# MC.net
KiCad netlist of a schematic drawn in EAGLE
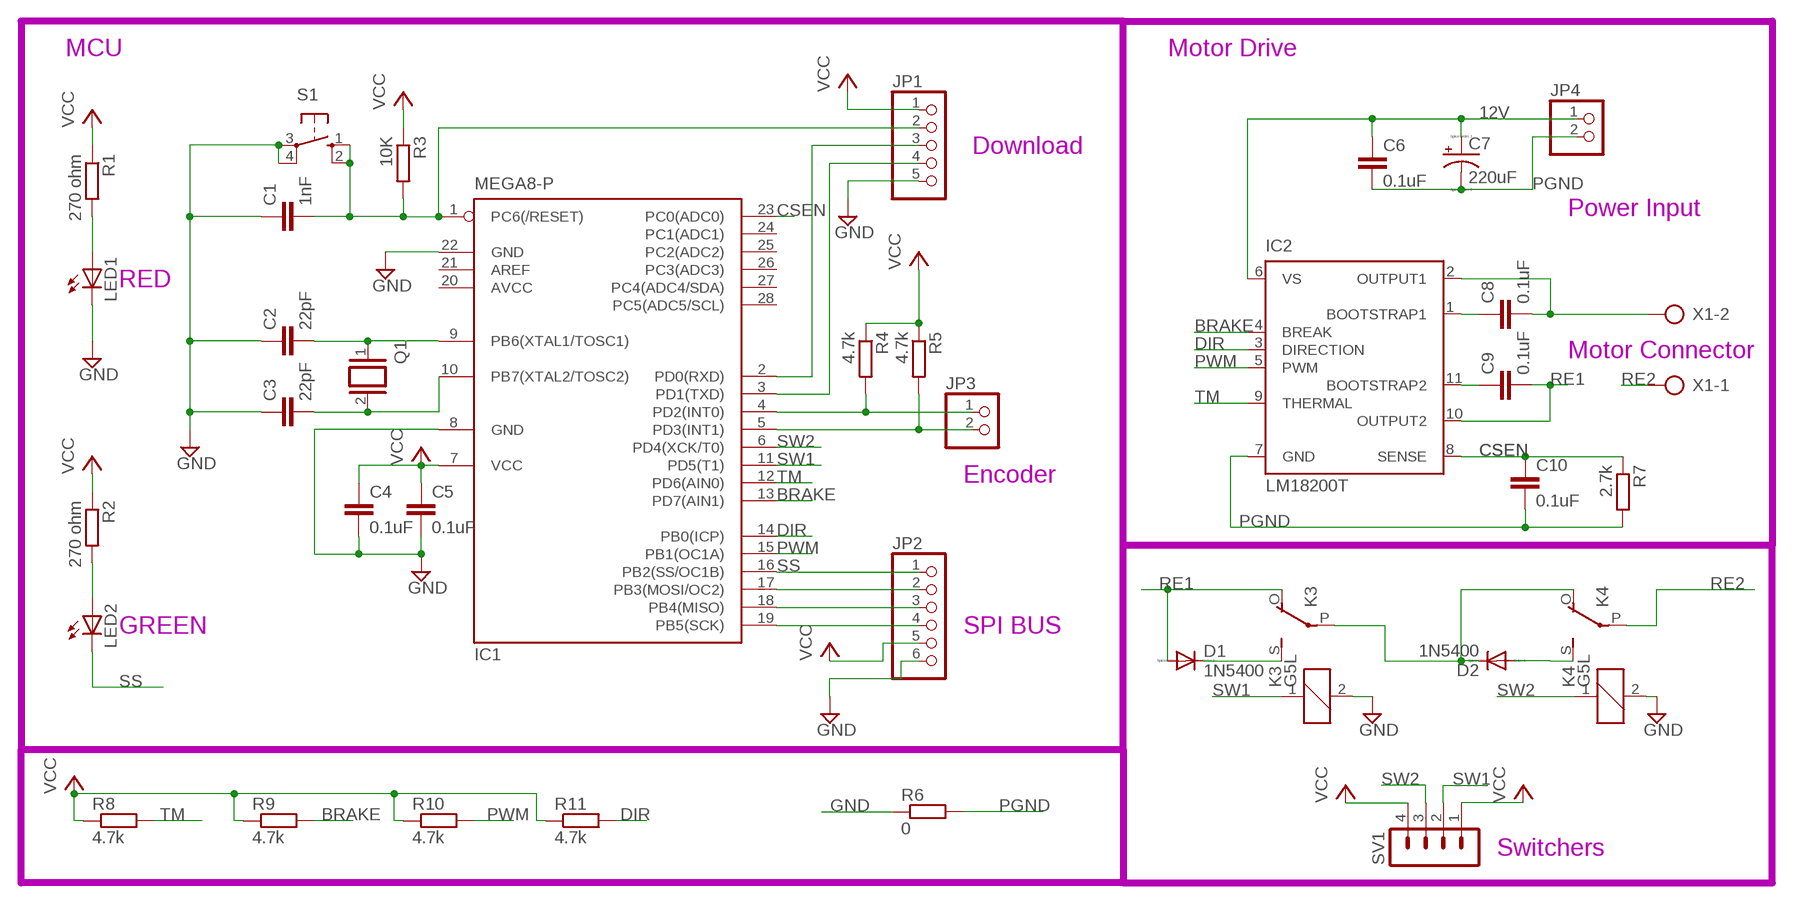
[diagram p0: schematic, sheet 1]

(export (version "E")
  (design (tool "Eeschema 10.0.6"))
  (components
    (comp (ref "C1")
      (value "1nF")
      (footprint "eagle-import:C0603")
      (libsource (lib "eagle-import") (part "C-EUC0603"))
    )
    (comp (ref "C2")
      (value "22pF")
      (footprint "eagle-import:C0603")
      (libsource (lib "eagle-import") (part "C-EUC0603"))
    )
    (comp (ref "C3")
      (value "22pF")
      (footprint "eagle-import:C0603")
      (libsource (lib "eagle-import") (part "C-EUC0603"))
    )
    (comp (ref "C4")
      (value "0.1uF")
      (footprint "eagle-import:C0603")
      (libsource (lib "eagle-import") (part "C-EUC0603"))
    )
    (comp (ref "C5")
      (value "0.1uF")
      (footprint "eagle-import:C0603")
      (libsource (lib "eagle-import") (part "C-EUC0603"))
    )
    (comp (ref "C6")
      (value "0.1uF")
      (footprint "eagle-import:C0603")
      (libsource (lib "eagle-import") (part "C-EUC0603"))
    )
    (comp (ref "C7")
      (value "220uF")
      (footprint "eagle-import:PANASONIC_F")
      (libsource (lib "eagle-import") (part "CPOL-USF"))
    )
    (comp (ref "C8")
      (value "0.1uF")
      (footprint "eagle-import:C0603")
      (libsource (lib "eagle-import") (part "C-EUC0603"))
    )
    (comp (ref "C9")
      (value "0.1uF")
      (footprint "eagle-import:C0603")
      (libsource (lib "eagle-import") (part "C-EUC0603"))
    )
    (comp (ref "C10")
      (value "0.1uF")
      (footprint "eagle-import:C0603")
      (libsource (lib "eagle-import") (part "C-EUC0603"))
    )
    (comp (ref "D1")
      (value "1N5400")
      (footprint "eagle-import:DO201-15")
      (libsource (lib "eagle-import") (part "1N5400"))
    )
    (comp (ref "D2")
      (value "1N5400")
      (footprint "eagle-import:DO201-15")
      (libsource (lib "eagle-import") (part "1N5400"))
    )
    (comp (ref "IC1")
      (value "MEGA8-P")
      (footprint "eagle-import:DIL28-3")
      (libsource (lib "eagle-import") (part "MEGA8-P"))
    )
    (comp (ref "IC2")
      (value "LM18200T")
      (footprint "eagle-import:TO-220-11")
      (libsource (lib "eagle-import") (part "LM18200T"))
    )
    (comp (ref "JP1")
      (value "PINHD-1X5")
      (footprint "eagle-import:1X05")
      (libsource (lib "eagle-import") (part "PINHD-1X5"))
    )
    (comp (ref "JP2")
      (value "PINHD-1X6")
      (footprint "eagle-import:1X06")
      (libsource (lib "eagle-import") (part "PINHD-1X6"))
    )
    (comp (ref "JP3")
      (value "PINHD-1X2")
      (footprint "eagle-import:1X02")
      (libsource (lib "eagle-import") (part "PINHD-1X2"))
    )
    (comp (ref "JP4")
      (value "PINHD-1X2")
      (footprint "eagle-import:1X02")
      (libsource (lib "eagle-import") (part "PINHD-1X2"))
    )
    (comp (ref "K3")
      (value "G5L")
      (footprint "eagle-import:G5LE")
      (libsource (lib "eagle-import") (part "G5L"))
    )
    (comp (ref "K4")
      (value "G5L")
      (footprint "eagle-import:G5LE")
      (libsource (lib "eagle-import") (part "G5L"))
    )
    (comp (ref "LED1")
      (value "LEDSML0603")
      (footprint "eagle-import:SML0603")
      (libsource (lib "eagle-import") (part "LEDSML0603"))
    )
    (comp (ref "LED2")
      (value "LEDSML0603")
      (footprint "eagle-import:SML0603")
      (libsource (lib "eagle-import") (part "LEDSML0603"))
    )
    (comp (ref "Q1")
      (value "XTAL/S")
      (footprint "eagle-import:QS")
      (libsource (lib "eagle-import") (part "XTAL/S"))
    )
    (comp (ref "R1")
      (value "270 ohm")
      (footprint "eagle-import:R0805")
      (libsource (lib "eagle-import") (part "R-EU_R0805"))
    )
    (comp (ref "R2")
      (value "270 ohm")
      (footprint "eagle-import:R0805")
      (libsource (lib "eagle-import") (part "R-EU_R0805"))
    )
    (comp (ref "R3")
      (value "10K")
      (footprint "eagle-import:R0805")
      (libsource (lib "eagle-import") (part "R-EU_R0805"))
    )
    (comp (ref "R4")
      (value "4.7k")
      (footprint "eagle-import:R0805")
      (libsource (lib "eagle-import") (part "R-EU_R0805"))
    )
    (comp (ref "R5")
      (value "4.7k")
      (footprint "eagle-import:R0805")
      (libsource (lib "eagle-import") (part "R-EU_R0805"))
    )
    (comp (ref "R6")
      (value "0")
      (footprint "eagle-import:R0603")
      (libsource (lib "eagle-import") (part "R-EU_R0603"))
    )
    (comp (ref "R7")
      (value "2.7k")
      (footprint "eagle-import:R0805")
      (libsource (lib "eagle-import") (part "R-EU_R0805"))
    )
    (comp (ref "R8")
      (value "4.7k")
      (footprint "eagle-import:R0805")
      (libsource (lib "eagle-import") (part "R-EU_R0805"))
    )
    (comp (ref "R9")
      (value "4.7k")
      (footprint "eagle-import:R0805")
      (libsource (lib "eagle-import") (part "R-EU_R0805"))
    )
    (comp (ref "R10")
      (value "4.7k")
      (footprint "eagle-import:0204_7")
      (libsource (lib "eagle-import") (part "R-EU_0204/7"))
    )
    (comp (ref "R11")
      (value "4.7k")
      (footprint "eagle-import:R0805")
      (libsource (lib "eagle-import") (part "R-EU_R0805"))
    )
    (comp (ref "S1")
      (value "10-XX")
      (footprint "eagle-import:B3F-10XX")
      (fields (field (name "MPN") "B3F-1000"))
      (libsource (lib "eagle-import") (part "10-XX"))
    )
    (comp (ref "SV1")
      (value "MA04-1")
      (footprint "eagle-import:MA04-1")
      (libsource (lib "eagle-import") (part "MA04-1"))
    )
    (comp (ref "X1")
      (value "AK300/2")
      (footprint "eagle-import:AK300_2")
      (libsource (lib "eagle-import") (part "AK300/2"))
    )
  )
  (nets
    (net (code "1") (name "/12V") (class "Default")
      (node (ref "C6") (pin "1") (pinfunction "1_1") (pintype "passive"))
      (node (ref "C7") (pin "+") (pinfunction "+_+") (pintype "passive"))
      (node (ref "IC2") (pin "6") (pinfunction "VS_6") (pintype "power_in"))
      (node (ref "JP4") (pin "1") (pinfunction "1_1") (pintype "passive"))
    )
    (net (code "2") (name "/AVCC") (class "Default")
      (node (ref "IC1") (pin "20") (pinfunction "AVCC_20") (pintype "power_in"))
    )
    (net (code "3") (name "/BRAKE") (class "Default")
      (node (ref "IC1") (pin "13") (pinfunction "PD7(AIN1)_13") (pintype "bidirectional"))
      (node (ref "IC2") (pin "4") (pinfunction "BREAK_4") (pintype "input"))
      (node (ref "R9") (pin "2") (pinfunction "2_2") (pintype "passive"))
    )
    (net (code "4") (name "/CSEN") (class "Default")
      (node (ref "C10") (pin "1") (pinfunction "1_1") (pintype "passive"))
      (node (ref "IC1") (pin "23") (pinfunction "PC0(ADC0)_23") (pintype "bidirectional"))
      (node (ref "IC2") (pin "8") (pinfunction "SENSE_8") (pintype "output"))
      (node (ref "R7") (pin "1") (pinfunction "1_1") (pintype "passive"))
    )
    (net (code "5") (name "/DIR") (class "Default")
      (node (ref "IC1") (pin "14") (pinfunction "PB0(ICP)_14") (pintype "bidirectional"))
      (node (ref "IC2") (pin "3") (pinfunction "DIRECTION_3") (pintype "input"))
      (node (ref "R11") (pin "2") (pinfunction "2_2") (pintype "passive"))
    )
    (net (code "6") (name "/PGND") (class "Default")
      (node (ref "C10") (pin "2") (pinfunction "2_2") (pintype "passive"))
      (node (ref "C6") (pin "2") (pinfunction "2_2") (pintype "passive"))
      (node (ref "C7") (pin "-") (pinfunction "-_-") (pintype "passive"))
      (node (ref "IC2") (pin "7") (pinfunction "GND_7") (pintype "power_in"))
      (node (ref "JP4") (pin "2") (pinfunction "2_2") (pintype "passive"))
      (node (ref "R6") (pin "2") (pinfunction "2_2") (pintype "passive"))
      (node (ref "R7") (pin "2") (pinfunction "2_2") (pintype "passive"))
    )
    (net (code "7") (name "/PWM") (class "Default")
      (node (ref "IC1") (pin "15") (pinfunction "PB1(OC1A)_15") (pintype "bidirectional"))
      (node (ref "IC2") (pin "5") (pinfunction "PWM_5") (pintype "input"))
      (node (ref "R10") (pin "2") (pinfunction "2_2") (pintype "passive"))
    )
    (net (code "8") (name "/RE1") (class "Default")
      (node (ref "C9") (pin "2") (pinfunction "2_2") (pintype "passive"))
      (node (ref "D1") (pin "A") (pinfunction "A_A") (pintype "passive"))
      (node (ref "IC2") (pin "10") (pinfunction "OUTPUT2_10") (pintype "output"))
      (node (ref "K3") (pin "O") (pinfunction "O_O") (pintype "passive"))
    )
    (net (code "9") (name "/RE2") (class "Default")
      (node (ref "K4") (pin "P") (pinfunction "P_P") (pintype "passive"))
      (node (ref "X1") (pin "1") (pinfunction "KL_1") (pintype "passive"))
    )
    (net (code "10") (name "/SS") (class "Default")
      (node (ref "IC1") (pin "16") (pinfunction "PB2(SS/OC1B)_16") (pintype "bidirectional"))
      (node (ref "JP2") (pin "1") (pinfunction "1_1") (pintype "passive"))
      (node (ref "LED2") (pin "C") (pinfunction "C_C") (pintype "passive"))
    )
    (net (code "11") (name "/SW1") (class "Default")
      (node (ref "IC1") (pin "11") (pinfunction "PD5(T1)_11") (pintype "bidirectional"))
      (node (ref "K3") (pin "1") (pinfunction "1_1") (pintype "passive"))
      (node (ref "SV1") (pin "2") (pinfunction "2_2") (pintype "passive"))
    )
    (net (code "12") (name "/SW2") (class "Default")
      (node (ref "IC1") (pin "6") (pinfunction "PD4(XCK/T0)_6") (pintype "bidirectional"))
      (node (ref "K4") (pin "1") (pinfunction "1_1") (pintype "passive"))
      (node (ref "SV1") (pin "3") (pinfunction "3_3") (pintype "passive"))
    )
    (net (code "13") (name "/TM") (class "Default")
      (node (ref "IC1") (pin "12") (pinfunction "PD6(AIN0)_12") (pintype "bidirectional"))
      (node (ref "IC2") (pin "9") (pinfunction "THERMAL_9") (pintype "output"))
      (node (ref "R8") (pin "2") (pinfunction "2_2") (pintype "passive"))
    )
    (net (code "14") (name "GND") (class "Default")
      (node (ref "C1") (pin "1") (pinfunction "1_1") (pintype "passive"))
      (node (ref "C2") (pin "1") (pinfunction "1_1") (pintype "passive"))
      (node (ref "C3") (pin "1") (pinfunction "1_1") (pintype "passive"))
      (node (ref "C4") (pin "2") (pinfunction "2_2") (pintype "passive"))
      (node (ref "C5") (pin "2") (pinfunction "2_2") (pintype "passive"))
      (node (ref "IC1") (pin "22") (pinfunction "GND_22") (pintype "power_in"))
      (node (ref "IC1") (pin "8") (pinfunction "GND_8") (pintype "power_in"))
      (node (ref "JP1") (pin "5") (pinfunction "5_5") (pintype "passive"))
      (node (ref "JP2") (pin "6") (pinfunction "6_6") (pintype "passive"))
      (node (ref "K3") (pin "2") (pinfunction "2_2") (pintype "passive"))
      (node (ref "K4") (pin "2") (pinfunction "2_2") (pintype "passive"))
      (node (ref "LED1") (pin "C") (pinfunction "C_C") (pintype "passive"))
      (node (ref "R6") (pin "1") (pinfunction "1_1") (pintype "passive"))
      (node (ref "S1") (pin "3") (pinfunction "P_3") (pintype "passive"))
      (node (ref "S1") (pin "4") (pinfunction "P1_4") (pintype "passive"))
    )
    (net (code "15") (name "Net-(D1-PadC)") (class "Default")
      (node (ref "D1") (pin "C") (pinfunction "C_C") (pintype "passive"))
      (node (ref "K3") (pin "S") (pinfunction "S_S") (pintype "passive"))
    )
    (net (code "16") (name "Net-(D2-PadA)") (class "Default")
      (node (ref "D2") (pin "A") (pinfunction "A_A") (pintype "passive"))
      (node (ref "K4") (pin "S") (pinfunction "S_S") (pintype "passive"))
    )
    (net (code "17") (name "Net-(D2-PadC)") (class "Default")
      (node (ref "D2") (pin "C") (pinfunction "C_C") (pintype "passive"))
      (node (ref "K3") (pin "P") (pinfunction "P_P") (pintype "passive"))
      (node (ref "K4") (pin "O") (pinfunction "O_O") (pintype "passive"))
    )
    (net (code "18") (name "Net-(IC1-PB3(MOSI{slash}OC2))") (class "Default")
      (node (ref "IC1") (pin "17") (pinfunction "PB3(MOSI/OC2)_17") (pintype "bidirectional"))
      (node (ref "JP2") (pin "2") (pinfunction "2_2") (pintype "passive"))
    )
    (net (code "19") (name "Net-(IC1-PB4(MISO))") (class "Default")
      (node (ref "IC1") (pin "18") (pinfunction "PB4(MISO)_18") (pintype "bidirectional"))
      (node (ref "JP2") (pin "3") (pinfunction "3_3") (pintype "passive"))
    )
    (net (code "20") (name "Net-(IC1-PB5(SCK))") (class "Default")
      (node (ref "IC1") (pin "19") (pinfunction "PB5(SCK)_19") (pintype "bidirectional"))
      (node (ref "JP2") (pin "4") (pinfunction "4_4") (pintype "passive"))
    )
    (net (code "21") (name "Net-(IC1-PB6(XTAL1{slash}TOSC1))") (class "Default")
      (node (ref "C2") (pin "2") (pinfunction "2_2") (pintype "passive"))
      (node (ref "IC1") (pin "9") (pinfunction "PB6(XTAL1/TOSC1)_9") (pintype "bidirectional"))
      (node (ref "Q1") (pin "1") (pinfunction "1_1") (pintype "passive"))
    )
    (net (code "22") (name "Net-(IC1-PB7(XTAL2{slash}TOSC2))") (class "Default")
      (node (ref "C3") (pin "2") (pinfunction "2_2") (pintype "passive"))
      (node (ref "IC1") (pin "10") (pinfunction "PB7(XTAL2/TOSC2)_10") (pintype "bidirectional"))
      (node (ref "Q1") (pin "2") (pinfunction "2_2") (pintype "passive"))
    )
    (net (code "23") (name "Net-(IC1-PC6({slash}RESET))") (class "Default")
      (node (ref "C1") (pin "2") (pinfunction "2_2") (pintype "passive"))
      (node (ref "IC1") (pin "1") (pinfunction "PC6(/RESET)_1") (pintype "bidirectional"))
      (node (ref "JP1") (pin "2") (pinfunction "2_2") (pintype "passive"))
      (node (ref "R3") (pin "2") (pinfunction "2_2") (pintype "passive"))
      (node (ref "S1") (pin "1") (pinfunction "S_1") (pintype "passive"))
      (node (ref "S1") (pin "2") (pinfunction "S1_2") (pintype "passive"))
    )
    (net (code "24") (name "Net-(IC1-PD0(RXD))") (class "Default")
      (node (ref "IC1") (pin "2") (pinfunction "PD0(RXD)_2") (pintype "bidirectional"))
      (node (ref "JP1") (pin "3") (pinfunction "3_3") (pintype "passive"))
    )
    (net (code "25") (name "Net-(IC1-PD1(TXD))") (class "Default")
      (node (ref "IC1") (pin "3") (pinfunction "PD1(TXD)_3") (pintype "bidirectional"))
      (node (ref "JP1") (pin "4") (pinfunction "4_4") (pintype "passive"))
    )
    (net (code "26") (name "Net-(IC1-PD2(INT0))") (class "Default")
      (node (ref "IC1") (pin "4") (pinfunction "PD2(INT0)_4") (pintype "bidirectional"))
      (node (ref "JP3") (pin "1") (pinfunction "1_1") (pintype "passive"))
      (node (ref "R4") (pin "2") (pinfunction "2_2") (pintype "passive"))
    )
    (net (code "27") (name "Net-(IC1-PD3(INT1))") (class "Default")
      (node (ref "IC1") (pin "5") (pinfunction "PD3(INT1)_5") (pintype "bidirectional"))
      (node (ref "JP3") (pin "2") (pinfunction "2_2") (pintype "passive"))
      (node (ref "R5") (pin "2") (pinfunction "2_2") (pintype "passive"))
    )
    (net (code "28") (name "Net-(IC2-BOOTSTRAP1)") (class "Default")
      (node (ref "C8") (pin "1") (pinfunction "1_1") (pintype "passive"))
      (node (ref "IC2") (pin "1") (pinfunction "BOOTSTRAP1_1") (pintype "input"))
    )
    (net (code "29") (name "Net-(IC2-BOOTSTRAP2)") (class "Default")
      (node (ref "C9") (pin "1") (pinfunction "1_1") (pintype "passive"))
      (node (ref "IC2") (pin "11") (pinfunction "BOOTSTRAP2_11") (pintype "input"))
    )
    (net (code "30") (name "Net-(IC2-OUTPUT1)") (class "Default")
      (node (ref "C8") (pin "2") (pinfunction "2_2") (pintype "passive"))
      (node (ref "IC2") (pin "2") (pinfunction "OUTPUT1_2") (pintype "output"))
      (node (ref "X1") (pin "2") (pinfunction "KL_2") (pintype "passive"))
    )
    (net (code "31") (name "Net-(LED1-PadA)") (class "Default")
      (node (ref "LED1") (pin "A") (pinfunction "A_A") (pintype "passive"))
      (node (ref "R1") (pin "2") (pinfunction "2_2") (pintype "passive"))
    )
    (net (code "32") (name "Net-(LED2-PadA)") (class "Default")
      (node (ref "LED2") (pin "A") (pinfunction "A_A") (pintype "passive"))
      (node (ref "R2") (pin "2") (pinfunction "2_2") (pintype "passive"))
    )
    (net (code "33") (name "VCC") (class "Default")
      (node (ref "C4") (pin "1") (pinfunction "1_1") (pintype "passive"))
      (node (ref "C5") (pin "1") (pinfunction "1_1") (pintype "passive"))
      (node (ref "IC1") (pin "7") (pinfunction "VCC_7") (pintype "power_in"))
      (node (ref "JP1") (pin "1") (pinfunction "1_1") (pintype "passive"))
      (node (ref "JP2") (pin "5") (pinfunction "5_5") (pintype "passive"))
      (node (ref "R1") (pin "1") (pinfunction "1_1") (pintype "passive"))
      (node (ref "R10") (pin "1") (pinfunction "1_1") (pintype "passive"))
      (node (ref "R11") (pin "1") (pinfunction "1_1") (pintype "passive"))
      (node (ref "R2") (pin "1") (pinfunction "1_1") (pintype "passive"))
      (node (ref "R3") (pin "1") (pinfunction "1_1") (pintype "passive"))
      (node (ref "R4") (pin "1") (pinfunction "1_1") (pintype "passive"))
      (node (ref "R5") (pin "1") (pinfunction "1_1") (pintype "passive"))
      (node (ref "R8") (pin "1") (pinfunction "1_1") (pintype "passive"))
      (node (ref "R9") (pin "1") (pinfunction "1_1") (pintype "passive"))
      (node (ref "SV1") (pin "1") (pinfunction "1_1") (pintype "passive"))
      (node (ref "SV1") (pin "4") (pinfunction "4_4") (pintype "passive"))
    )
    (net (code "34") (name "unconnected-(IC1-AREF-Pad21)") (class "Default")
      (node (ref "IC1") (pin "21") (pinfunction "AREF_21") (pintype "passive"))
    )
    (net (code "35") (name "unconnected-(IC1-PC1(ADC1)-Pad24)") (class "Default")
      (node (ref "IC1") (pin "24") (pinfunction "PC1(ADC1)_24") (pintype "bidirectional"))
    )
    (net (code "36") (name "unconnected-(IC1-PC2(ADC2)-Pad25)") (class "Default")
      (node (ref "IC1") (pin "25") (pinfunction "PC2(ADC2)_25") (pintype "bidirectional"))
    )
    (net (code "37") (name "unconnected-(IC1-PC3(ADC3)-Pad26)") (class "Default")
      (node (ref "IC1") (pin "26") (pinfunction "PC3(ADC3)_26") (pintype "bidirectional"))
    )
    (net (code "38") (name "unconnected-(IC1-PC4(ADC4{slash}SDA)-Pad27)") (class "Default")
      (node (ref "IC1") (pin "27") (pinfunction "PC4(ADC4/SDA)_27") (pintype "bidirectional"))
    )
    (net (code "39") (name "unconnected-(IC1-PC5(ADC5{slash}SCL)-Pad28)") (class "Default")
      (node (ref "IC1") (pin "28") (pinfunction "PC5(ADC5/SCL)_28") (pintype "bidirectional"))
    )
  )
)
